# switch_tx.net
KiCad netlist of a schematic drawn in Altium Designer
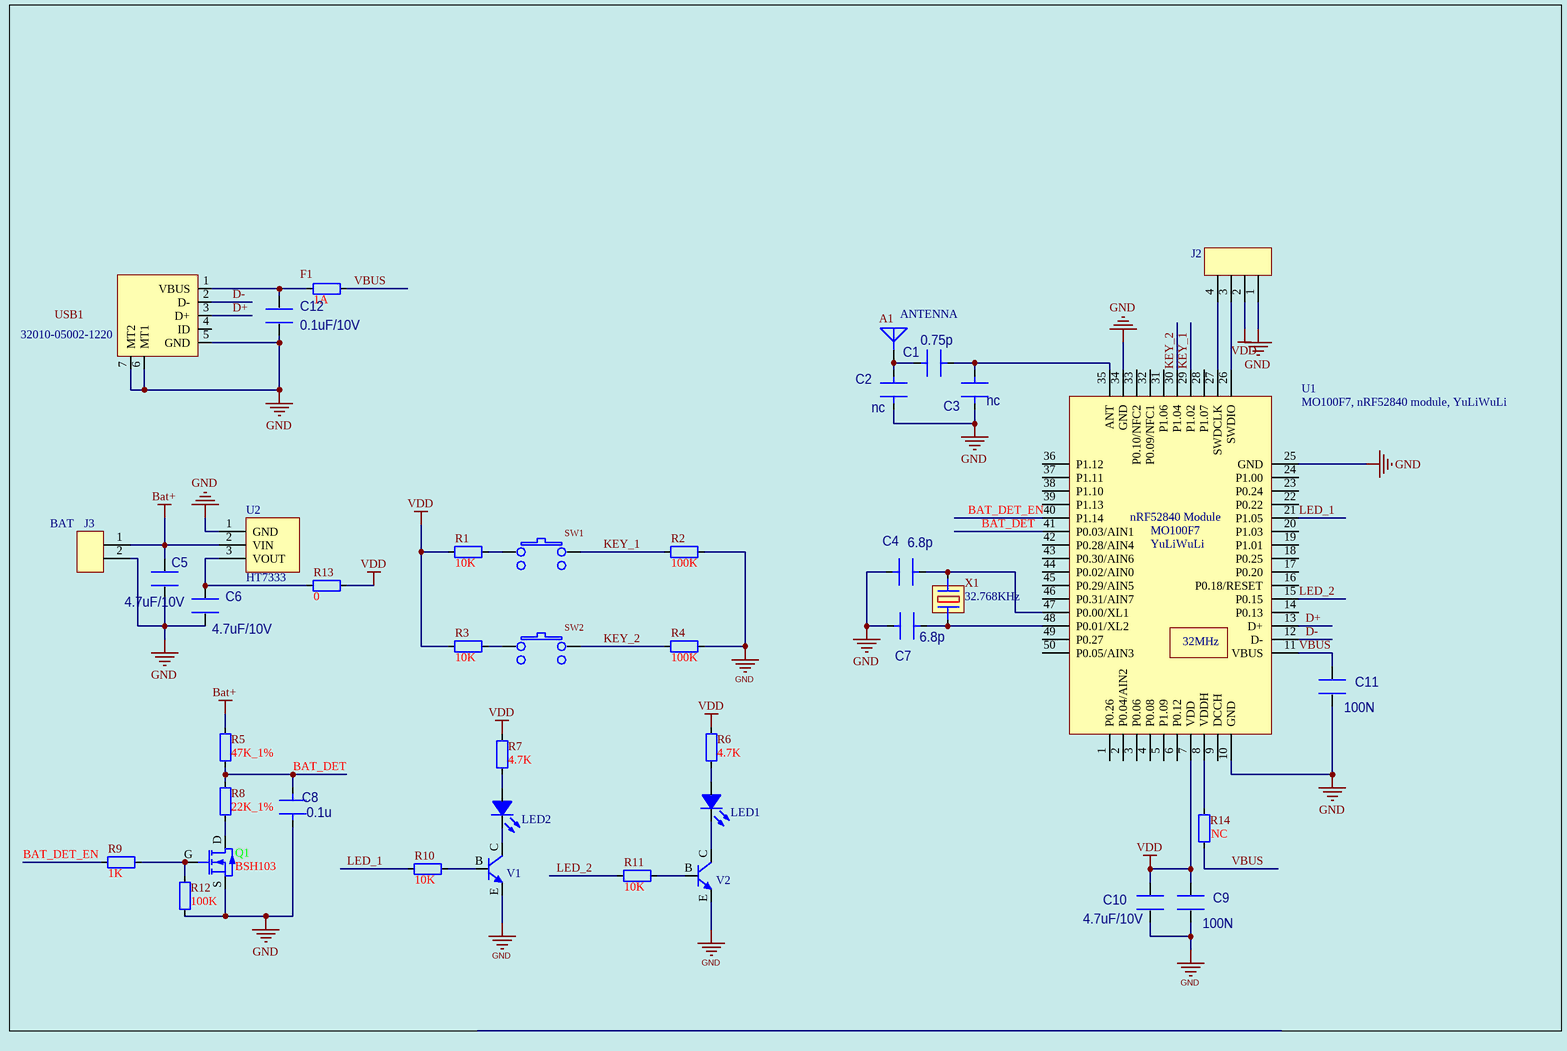
[diagram p0: switch_tx.SchDoc]

(export (version "E")
  (design (tool "Eeschema 10.0.6"))
  (components
    (comp (ref "A1")
      (value "ANTENNA")
      (footprint "AN2")
      (description "PCB Antenna")
      (libsource (lib "switch") (part "ANTENNA"))
    )
    (comp (ref "C1")
      (value "0.75p")
      (footprint "cap0603(1608)")
      (fields (field (name "Comment") "CAP"))
      (libsource (lib "switch_tx") (part "CAP"))
    )
    (comp (ref "C2")
      (value "nc")
      (footprint "cap0603(1608)")
      (fields (field (name "Comment") "CAP"))
      (libsource (lib "switch_tx") (part "CAP"))
    )
    (comp (ref "C3")
      (value "nc")
      (footprint "cap0603(1608)")
      (fields (field (name "Comment") "CAP"))
      (libsource (lib "switch_tx") (part "CAP"))
    )
    (comp (ref "C4")
      (value "6.8p")
      (footprint "cap0603(1608)")
      (fields (field (name "Comment") "CAP"))
      (libsource (lib "switch_tx") (part "CAP"))
    )
    (comp (ref "C5")
      (value "4.7uF/10V")
      (footprint "cap0603(1608)")
      (fields (field (name "Comment") "CC103"))
      (libsource (lib "*") (part "CC103"))
    )
    (comp (ref "C6")
      (value "4.7uF/10V")
      (footprint "cap0603(1608)")
      (fields (field (name "Comment") "CC103"))
      (libsource (lib "*") (part "CC103"))
    )
    (comp (ref "C7")
      (value "6.8p")
      (footprint "cap0603(1608)")
      (fields (field (name "Comment") "CAP"))
      (libsource (lib "switch_tx") (part "CAP"))
    )
    (comp (ref "C8")
      (value "0.1u")
      (footprint "cap0603(1608)")
      (fields (field (name "Comment") "CAP"))
      (libsource (lib "switch_tx") (part "CAP"))
    )
    (comp (ref "C9")
      (value "100N")
      (footprint "cap0603(1608)")
      (fields (field (name "Comment") "CC103"))
      (libsource (lib "*") (part "CC103"))
    )
    (comp (ref "C10")
      (value "4.7uF/10V")
      (footprint "cap0603(1608)")
      (fields (field (name "Comment") "CC103"))
      (libsource (lib "*") (part "CC103"))
    )
    (comp (ref "C11")
      (value "100N")
      (footprint "cap0603(1608)")
      (fields (field (name "Comment") "CC103"))
      (libsource (lib "*") (part "CC103"))
    )
    (comp (ref "C12")
      (value "0.1uF/10V")
      (footprint "cap0603(1608)")
      (fields (field (name "Comment") "CC103"))
      (libsource (lib "*") (part "CC103"))
    )
    (comp (ref "F1")
      (value "1A")
      (footprint "RESC0603(1608)_N")
      (fields (field (name "PUBLISHER") "i3tex"))
      (libsource (lib "") (part "Res_2"))
    )
    (comp (ref "J2") (value "HEAD-1x4") (footprint "HEAD-1x4-2.54") (libsource (lib "vod") (part "HEAD-1x4")))
    (comp (ref "J3") (value "BAT") (footprint "HEAD-1x2-2.54") (libsource (lib "vod") (part "HEAD-1x2")))
    (comp (ref "LED1") (value "LED") (footprint "led_3mm") (libsource (lib "vod") (part "LED")))
    (comp (ref "LED2") (value "LED") (footprint "led_3mm") (libsource (lib "vod") (part "LED")))
    (comp (ref "Q1")
      (value "BSH103")
      (footprint "SOT-23-mosfet")
      (description "N channel MOSFET, 20V, 3.7A, 39mohm")
      (fields (field (name "PUBLISHER") "Altium Limited"))
      (libsource (lib "switch_tx") (part "MOSFET-N"))
    )
    (comp (ref "R1")
      (value "10K")
      (footprint "RESC0603(1608)_N")
      (fields (field (name "PUBLISHER") "i3tex"))
      (libsource (lib "") (part "Res_2"))
    )
    (comp (ref "R2")
      (value "100K")
      (footprint "RESC0603(1608)_N")
      (fields (field (name "PUBLISHER") "i3tex"))
      (libsource (lib "") (part "Res_2"))
    )
    (comp (ref "R3")
      (value "10K")
      (footprint "RESC0603(1608)_N")
      (fields (field (name "PUBLISHER") "i3tex"))
      (libsource (lib "") (part "Res_2"))
    )
    (comp (ref "R4")
      (value "100K")
      (footprint "RESC0603(1608)_N")
      (fields (field (name "PUBLISHER") "i3tex"))
      (libsource (lib "") (part "Res_1"))
    )
    (comp (ref "R5")
      (value "47K_1%")
      (footprint "RESC0603(1608)_N")
      (fields (field (name "PUBLISHER") "i3tex"))
      (libsource (lib "") (part "Res_3"))
    )
    (comp (ref "R6")
      (value "4.7K")
      (footprint "RESC0603(1608)_N")
      (fields (field (name "PUBLISHER") "i3tex"))
      (libsource (lib "switch_tx") (part "Res"))
    )
    (comp (ref "R7")
      (value "4.7K")
      (footprint "RESC0603(1608)_N")
      (fields (field (name "PUBLISHER") "i3tex"))
      (libsource (lib "switch_tx") (part "Res"))
    )
    (comp (ref "R8")
      (value "22K_1%")
      (footprint "RESC0603(1608)_N")
      (fields (field (name "PUBLISHER") "i3tex"))
      (libsource (lib "switch_tx") (part "Res"))
    )
    (comp (ref "R9")
      (value "1K")
      (footprint "RESC0603(1608)_N")
      (fields (field (name "PUBLISHER") "i3tex"))
      (libsource (lib "") (part "Res_2"))
    )
    (comp (ref "R10")
      (value "10K")
      (footprint "RESC0603(1608)_N")
      (fields (field (name "PUBLISHER") "i3tex"))
      (libsource (lib "") (part "Res_1"))
    )
    (comp (ref "R11")
      (value "10K")
      (footprint "RESC0603(1608)_N")
      (fields (field (name "PUBLISHER") "i3tex"))
      (libsource (lib "") (part "Res_1"))
    )
    (comp (ref "R12")
      (value "100K")
      (footprint "RESC0603(1608)_N")
      (fields (field (name "PUBLISHER") "i3tex"))
      (libsource (lib "switch_tx") (part "Res"))
    )
    (comp (ref "R13")
      (value "0")
      (footprint "RESC0603(1608)_N")
      (fields (field (name "PUBLISHER") "i3tex"))
      (libsource (lib "") (part "Res_2"))
    )
    (comp (ref "R14")
      (value "NC")
      (footprint "RESC0603(1608)_N")
      (fields (field (name "PUBLISHER") "i3tex"))
      (libsource (lib "switch_tx") (part "Res"))
    )
    (comp (ref "SW1")
      (value "TACT")
      (footprint "SW_6X6X5mm")
      (libsource (lib "Yihom_library") (part "SWITCH_TACT_SPST_2-2_PINS"))
    )
    (comp (ref "SW2")
      (value "TACT")
      (footprint "SW_6X6X5mm")
      (libsource (lib "Yihom_library") (part "SWITCH_TACT_SPST_2-2_PINS"))
    )
    (comp (ref "U1")
      (value "MO100F7, nRF52840 module, YuLiWuLi")
      (footprint "MO100F7")
      (libsource (lib "switch_tx") (part "MO100F7"))
    )
    (comp (ref "U2") (value "HT7333") (footprint "HT7333-SOT-89") (libsource (lib "vod") (part "HT7333")))
    (comp (ref "USB1")
      (value "32010-05002-1220")
      (footprint "Micro USB")
      (description "Mirco_USB_5S_B")
      (libsource (lib "USB_Connector") (part "Component_1"))
    )
    (comp (ref "V1") (value "NPN") (footprint "SOT-23-NPN") (libsource (lib "vod") (part "NPN")))
    (comp (ref "V2") (value "NPN") (footprint "SOT-23-NPN") (libsource (lib "vod") (part "NPN")))
    (comp (ref "X1")
      (value "32.768KHz")
      (footprint "32.768_A")
      (libsource (lib "switch_tx") (part "Crystal_2PIN"))
    )
  )
  (nets
    (net (code "1") (name "/BAT_DET") (class "Default")
      (node (ref "C8") (pin "2") (pinfunction "2_2") (pintype "passive"))
      (node (ref "R5") (pin "2") (pinfunction "2_2") (pintype "passive"))
      (node (ref "R8") (pin "2") (pinfunction "2_2") (pintype "passive"))
      (node (ref "U1") (pin "41") (pinfunction "P0.03/AIN1_41") (pintype "passive"))
    )
    (net (code "2") (name "/BAT_DET_EN") (class "Default")
      (node (ref "R9") (pin "2") (pinfunction "2_2") (pintype "passive"))
      (node (ref "U1") (pin "40") (pinfunction "P1.14_40") (pintype "passive"))
    )
    (net (code "3") (name "/D+") (class "Default")
      (node (ref "U1") (pin "13") (pinfunction "D+_13") (pintype "passive"))
      (node (ref "USB1") (pin "3") (pinfunction "D+_3") (pintype "passive"))
    )
    (net (code "4") (name "/D-") (class "Default")
      (node (ref "U1") (pin "12") (pinfunction "D-_12") (pintype "passive"))
      (node (ref "USB1") (pin "2") (pinfunction "D-_2") (pintype "passive"))
    )
    (net (code "5") (name "/KEY_1") (class "Default")
      (node (ref "R2") (pin "2") (pinfunction "2_2") (pintype "passive"))
      (node (ref "SW1") (pin "1") (pinfunction "1_1") (pintype "passive"))
      (node (ref "U1") (pin "29") (pinfunction "P1.02_29") (pintype "passive"))
    )
    (net (code "6") (name "/KEY_2") (class "Default")
      (node (ref "R4") (pin "1") (pinfunction "1_1") (pintype "passive"))
      (node (ref "SW2") (pin "1") (pinfunction "1_1") (pintype "passive"))
      (node (ref "U1") (pin "30") (pinfunction "P1.04_30") (pintype "passive"))
    )
    (net (code "7") (name "/LED_1") (class "Default")
      (node (ref "R10") (pin "1") (pinfunction "1_1") (pintype "passive"))
      (node (ref "U1") (pin "21") (pinfunction "P1.05_21") (pintype "passive"))
    )
    (net (code "8") (name "/LED_2") (class "Default")
      (node (ref "R11") (pin "1") (pinfunction "1_1") (pintype "passive"))
      (node (ref "U1") (pin "15") (pinfunction "P0.15_15") (pintype "passive"))
    )
    (net (code "9") (name "/VBUS") (class "Default")
      (node (ref "C11") (pin "1") (pinfunction "1_1") (pintype "passive"))
      (node (ref "F1") (pin "1") (pinfunction "1_1") (pintype "passive"))
      (node (ref "R14") (pin "1") (pinfunction "1_1") (pintype "passive"))
      (node (ref "U1") (pin "11") (pinfunction "VBUS_11") (pintype "passive"))
    )
    (net (code "10") (name "Bat+") (class "Default")
      (node (ref "C5") (pin "1") (pinfunction "1_1") (pintype "passive"))
      (node (ref "J3") (pin "1") (pintype "passive"))
      (node (ref "R5") (pin "1") (pinfunction "1_1") (pintype "passive"))
      (node (ref "U2") (pin "2") (pinfunction "VIN_2") (pintype "passive"))
    )
    (net (code "11") (name "GND") (class "Default")
      (node (ref "C10") (pin "2") (pinfunction "2_2") (pintype "passive"))
      (node (ref "C11") (pin "2") (pinfunction "2_2") (pintype "passive"))
      (node (ref "C12") (pin "2") (pinfunction "2_2") (pintype "passive"))
      (node (ref "C2") (pin "1") (pinfunction "1_1") (pintype "passive"))
      (node (ref "C3") (pin "2") (pinfunction "2_2") (pintype "passive"))
      (node (ref "C4") (pin "1") (pinfunction "1_1") (pintype "passive"))
      (node (ref "C5") (pin "2") (pinfunction "2_2") (pintype "passive"))
      (node (ref "C6") (pin "2") (pinfunction "2_2") (pintype "passive"))
      (node (ref "C7") (pin "1") (pinfunction "1_1") (pintype "passive"))
      (node (ref "C8") (pin "1") (pinfunction "1_1") (pintype "passive"))
      (node (ref "C9") (pin "2") (pinfunction "2_2") (pintype "passive"))
      (node (ref "J2") (pin "1") (pintype "passive"))
      (node (ref "J3") (pin "2") (pintype "passive"))
      (node (ref "Q1") (pin "S") (pinfunction "S_S") (pintype "passive"))
      (node (ref "R12") (pin "1") (pinfunction "1_1") (pintype "passive"))
      (node (ref "R2") (pin "1") (pinfunction "1_1") (pintype "passive"))
      (node (ref "R4") (pin "2") (pinfunction "2_2") (pintype "passive"))
      (node (ref "U1") (pin "10") (pinfunction "GND_10") (pintype "passive"))
      (node (ref "U1") (pin "25") (pinfunction "GND_25") (pintype "passive"))
      (node (ref "U1") (pin "34") (pinfunction "GND_34") (pintype "passive"))
      (node (ref "U2") (pin "1") (pinfunction "GND_1") (pintype "passive"))
      (node (ref "USB1") (pin "5") (pinfunction "GND_5") (pintype "passive"))
      (node (ref "USB1") (pin "6") (pinfunction "MT1_6") (pintype "passive"))
      (node (ref "USB1") (pin "7") (pinfunction "MT2_7") (pintype "passive"))
      (node (ref "V1") (pin "E") (pinfunction "E_E") (pintype "passive"))
      (node (ref "V2") (pin "E") (pinfunction "E_E") (pintype "passive"))
    )
    (net (code "12") (name "Net-(A1-A)") (class "Default")
      (node (ref "A1") (pin "1") (pinfunction "A_1") (pintype "passive"))
      (node (ref "C1") (pin "1") (pinfunction "1_1") (pintype "passive"))
      (node (ref "C2") (pin "2") (pinfunction "2_2") (pintype "passive"))
    )
    (net (code "13") (name "Net-(LED1-A)") (class "Default")
      (node (ref "LED1") (pin "1") (pinfunction "A_1") (pintype "passive"))
      (node (ref "R6") (pin "1") (pinfunction "1_1") (pintype "passive"))
    )
    (net (code "14") (name "Net-(LED1-K)") (class "Default")
      (node (ref "LED1") (pin "2") (pinfunction "K_2") (pintype "passive"))
      (node (ref "V2") (pin "C") (pinfunction "C_C") (pintype "passive"))
    )
    (net (code "15") (name "Net-(LED2-A)") (class "Default")
      (node (ref "LED2") (pin "1") (pinfunction "A_1") (pintype "passive"))
      (node (ref "R7") (pin "1") (pinfunction "1_1") (pintype "passive"))
    )
    (net (code "16") (name "Net-(LED2-K)") (class "Default")
      (node (ref "LED2") (pin "2") (pinfunction "K_2") (pintype "passive"))
      (node (ref "V1") (pin "C") (pinfunction "C_C") (pintype "passive"))
    )
    (net (code "17") (name "Net-(Q1-PadD)") (class "Default")
      (node (ref "Q1") (pin "D") (pinfunction "D_D") (pintype "passive"))
      (node (ref "R8") (pin "1") (pinfunction "1_1") (pintype "passive"))
    )
    (net (code "18") (name "Net-(Q1-PadG)") (class "Default")
      (node (ref "Q1") (pin "G") (pinfunction "G_G") (pintype "passive"))
      (node (ref "R12") (pin "2") (pinfunction "2_2") (pintype "passive"))
      (node (ref "R9") (pin "1") (pinfunction "1_1") (pintype "passive"))
    )
    (net (code "19") (name "Net-(R1-Pad1)") (class "Default")
      (node (ref "R1") (pin "1") (pinfunction "1_1") (pintype "passive"))
      (node (ref "SW1") (pin "2") (pinfunction "2_2") (pintype "passive"))
    )
    (net (code "20") (name "Net-(R3-Pad1)") (class "Default")
      (node (ref "R3") (pin "1") (pinfunction "1_1") (pintype "passive"))
      (node (ref "SW2") (pin "2") (pinfunction "2_2") (pintype "passive"))
    )
    (net (code "21") (name "Net-(R10-Pad2)") (class "Default")
      (node (ref "R10") (pin "2") (pinfunction "2_2") (pintype "passive"))
      (node (ref "V1") (pin "B") (pinfunction "B_B") (pintype "passive"))
    )
    (net (code "22") (name "Net-(R11-Pad2)") (class "Default")
      (node (ref "R11") (pin "2") (pinfunction "2_2") (pintype "passive"))
      (node (ref "V2") (pin "B") (pinfunction "B_B") (pintype "passive"))
    )
    (net (code "23") (name "Net-(U1-ANT)") (class "Default")
      (node (ref "C1") (pin "2") (pinfunction "2_2") (pintype "passive"))
      (node (ref "C3") (pin "1") (pinfunction "1_1") (pintype "passive"))
      (node (ref "U1") (pin "35") (pinfunction "ANT_35") (pintype "passive"))
    )
    (net (code "24") (name "Net-(U1-P0.00{slash}XL1)") (class "Default")
      (node (ref "C4") (pin "2") (pinfunction "2_2") (pintype "passive"))
      (node (ref "U1") (pin "47") (pinfunction "P0.00/XL1_47") (pintype "passive"))
      (node (ref "X1") (pin "2") (pinfunction "OUT_2") (pintype "passive"))
    )
    (net (code "25") (name "Net-(U1-P0.01{slash}XL2)") (class "Default")
      (node (ref "C7") (pin "2") (pinfunction "2_2") (pintype "passive"))
      (node (ref "U1") (pin "48") (pinfunction "P0.01/XL2_48") (pintype "passive"))
      (node (ref "X1") (pin "1") (pinfunction "IN_1") (pintype "passive"))
    )
    (net (code "26") (name "Net-(U1-SWDCLK)") (class "Default")
      (node (ref "J2") (pin "4") (pintype "passive"))
      (node (ref "U1") (pin "27") (pinfunction "SWDCLK_27") (pintype "passive"))
    )
    (net (code "27") (name "Net-(U1-SWDIO)") (class "Default")
      (node (ref "J2") (pin "3") (pintype "passive"))
      (node (ref "U1") (pin "26") (pinfunction "SWDIO_26") (pintype "passive"))
    )
    (net (code "28") (name "Net-(U1-VDDH)") (class "Default")
      (node (ref "R14") (pin "2") (pinfunction "2_2") (pintype "passive"))
      (node (ref "U1") (pin "8") (pinfunction "VDDH_8") (pintype "passive"))
    )
    (net (code "29") (name "Net-(U2-VOUT)") (class "Default")
      (node (ref "C6") (pin "1") (pinfunction "1_1") (pintype "passive"))
      (node (ref "R13") (pin "2") (pinfunction "2_2") (pintype "passive"))
      (node (ref "U2") (pin "3") (pinfunction "VOUT_3") (pintype "passive"))
    )
    (net (code "30") (name "Net-(USB1-VBUS)") (class "Default")
      (node (ref "C12") (pin "1") (pinfunction "1_1") (pintype "passive"))
      (node (ref "F1") (pin "2") (pinfunction "2_2") (pintype "passive"))
      (node (ref "USB1") (pin "1") (pinfunction "VBUS_1") (pintype "passive"))
    )
    (net (code "31") (name "VDD") (class "Default")
      (node (ref "C10") (pin "1") (pinfunction "1_1") (pintype "passive"))
      (node (ref "C9") (pin "1") (pinfunction "1_1") (pintype "passive"))
      (node (ref "J2") (pin "2") (pintype "passive"))
      (node (ref "R1") (pin "2") (pinfunction "2_2") (pintype "passive"))
      (node (ref "R13") (pin "1") (pinfunction "1_1") (pintype "passive"))
      (node (ref "R3") (pin "2") (pinfunction "2_2") (pintype "passive"))
      (node (ref "R6") (pin "2") (pinfunction "2_2") (pintype "passive"))
      (node (ref "R7") (pin "2") (pinfunction "2_2") (pintype "passive"))
      (node (ref "U1") (pin "7") (pinfunction "VDD_7") (pintype "passive"))
    )
    (net (code "32") (name "unconnected-(U1-DCCH-Pad9)") (class "Default")
      (node (ref "U1") (pin "9") (pinfunction "DCCH_9") (pintype "passive"))
    )
    (net (code "33") (name "unconnected-(U1-P0.02{slash}AIN0-Pad44)") (class "Default")
      (node (ref "U1") (pin "44") (pinfunction "P0.02/AIN0_44") (pintype "passive"))
    )
    (net (code "34") (name "unconnected-(U1-P0.04{slash}AIN2-Pad2)") (class "Default")
      (node (ref "U1") (pin "2") (pinfunction "P0.04/AIN2_2") (pintype "passive"))
    )
    (net (code "35") (name "unconnected-(U1-P0.05{slash}AIN3-Pad50)") (class "Default")
      (node (ref "U1") (pin "50") (pinfunction "P0.05/AIN3_50") (pintype "passive"))
    )
    (net (code "36") (name "unconnected-(U1-P0.06-Pad3)") (class "Default")
      (node (ref "U1") (pin "3") (pinfunction "P0.06_3") (pintype "passive"))
    )
    (net (code "37") (name "unconnected-(U1-P0.08-Pad4)") (class "Default")
      (node (ref "U1") (pin "4") (pinfunction "P0.08_4") (pintype "passive"))
    )
    (net (code "38") (name "unconnected-(U1-P0.09{slash}NFC1-Pad32)") (class "Default")
      (node (ref "U1") (pin "32") (pinfunction "P0.09/NFC1_32") (pintype "passive"))
    )
    (net (code "39") (name "unconnected-(U1-P0.10{slash}NFC2-Pad33)") (class "Default")
      (node (ref "U1") (pin "33") (pinfunction "P0.10/NFC2_33") (pintype "passive"))
    )
    (net (code "40") (name "unconnected-(U1-P0.12-Pad6)") (class "Default")
      (node (ref "U1") (pin "6") (pinfunction "P0.12_6") (pintype "passive"))
    )
    (net (code "41") (name "unconnected-(U1-P0.13-Pad14)") (class "Default")
      (node (ref "U1") (pin "14") (pinfunction "P0.13_14") (pintype "passive"))
    )
    (net (code "42") (name "unconnected-(U1-P0.18{slash}RESET-Pad16)") (class "Default")
      (node (ref "U1") (pin "16") (pinfunction "P0.18/RESET_16") (pintype "passive"))
    )
    (net (code "43") (name "unconnected-(U1-P0.20-Pad17)") (class "Default")
      (node (ref "U1") (pin "17") (pinfunction "P0.20_17") (pintype "passive"))
    )
    (net (code "44") (name "unconnected-(U1-P0.22-Pad22)") (class "Default")
      (node (ref "U1") (pin "22") (pinfunction "P0.22_22") (pintype "passive"))
    )
    (net (code "45") (name "unconnected-(U1-P0.24-Pad23)") (class "Default")
      (node (ref "U1") (pin "23") (pinfunction "P0.24_23") (pintype "passive"))
    )
    (net (code "46") (name "unconnected-(U1-P0.25-Pad18)") (class "Default")
      (node (ref "U1") (pin "18") (pinfunction "P0.25_18") (pintype "passive"))
    )
    (net (code "47") (name "unconnected-(U1-P0.26-Pad1)") (class "Default")
      (node (ref "U1") (pin "1") (pinfunction "P0.26_1") (pintype "passive"))
    )
    (net (code "48") (name "unconnected-(U1-P0.27-Pad49)") (class "Default")
      (node (ref "U1") (pin "49") (pinfunction "P0.27_49") (pintype "passive"))
    )
    (net (code "49") (name "unconnected-(U1-P0.28{slash}AIN4-Pad42)") (class "Default")
      (node (ref "U1") (pin "42") (pinfunction "P0.28/AIN4_42") (pintype "passive"))
    )
    (net (code "50") (name "unconnected-(U1-P0.29{slash}AIN5-Pad45)") (class "Default")
      (node (ref "U1") (pin "45") (pinfunction "P0.29/AIN5_45") (pintype "passive"))
    )
    (net (code "51") (name "unconnected-(U1-P0.30{slash}AIN6-Pad43)") (class "Default")
      (node (ref "U1") (pin "43") (pinfunction "P0.30/AIN6_43") (pintype "passive"))
    )
    (net (code "52") (name "unconnected-(U1-P0.31{slash}AIN7-Pad46)") (class "Default")
      (node (ref "U1") (pin "46") (pinfunction "P0.31/AIN7_46") (pintype "passive"))
    )
    (net (code "53") (name "unconnected-(U1-P1.00-Pad24)") (class "Default")
      (node (ref "U1") (pin "24") (pinfunction "P1.00_24") (pintype "passive"))
    )
    (net (code "54") (name "unconnected-(U1-P1.01-Pad19)") (class "Default")
      (node (ref "U1") (pin "19") (pinfunction "P1.01_19") (pintype "passive"))
    )
    (net (code "55") (name "unconnected-(U1-P1.03-Pad20)") (class "Default")
      (node (ref "U1") (pin "20") (pinfunction "P1.03_20") (pintype "passive"))
    )
    (net (code "56") (name "unconnected-(U1-P1.06-Pad31)") (class "Default")
      (node (ref "U1") (pin "31") (pinfunction "P1.06_31") (pintype "passive"))
    )
    (net (code "57") (name "unconnected-(U1-P1.07-Pad28)") (class "Default")
      (node (ref "U1") (pin "28") (pinfunction "P1.07_28") (pintype "passive"))
    )
    (net (code "58") (name "unconnected-(U1-P1.09-Pad5)") (class "Default")
      (node (ref "U1") (pin "5") (pinfunction "P1.09_5") (pintype "passive"))
    )
    (net (code "59") (name "unconnected-(U1-P1.10-Pad38)") (class "Default")
      (node (ref "U1") (pin "38") (pinfunction "P1.10_38") (pintype "passive"))
    )
    (net (code "60") (name "unconnected-(U1-P1.11-Pad37)") (class "Default")
      (node (ref "U1") (pin "37") (pinfunction "P1.11_37") (pintype "passive"))
    )
    (net (code "61") (name "unconnected-(U1-P1.12-Pad36)") (class "Default")
      (node (ref "U1") (pin "36") (pinfunction "P1.12_36") (pintype "passive"))
    )
    (net (code "62") (name "unconnected-(U1-P1.13-Pad39)") (class "Default")
      (node (ref "U1") (pin "39") (pinfunction "P1.13_39") (pintype "passive"))
    )
    (net (code "63") (name "unconnected-(USB1-ID-Pad4)") (class "Default")
      (node (ref "USB1") (pin "4") (pinfunction "ID_4") (pintype "passive"))
    )
  )
)
